# DCDC-LMR16030.net
KiCad netlist of a schematic drawn in Altium Designer
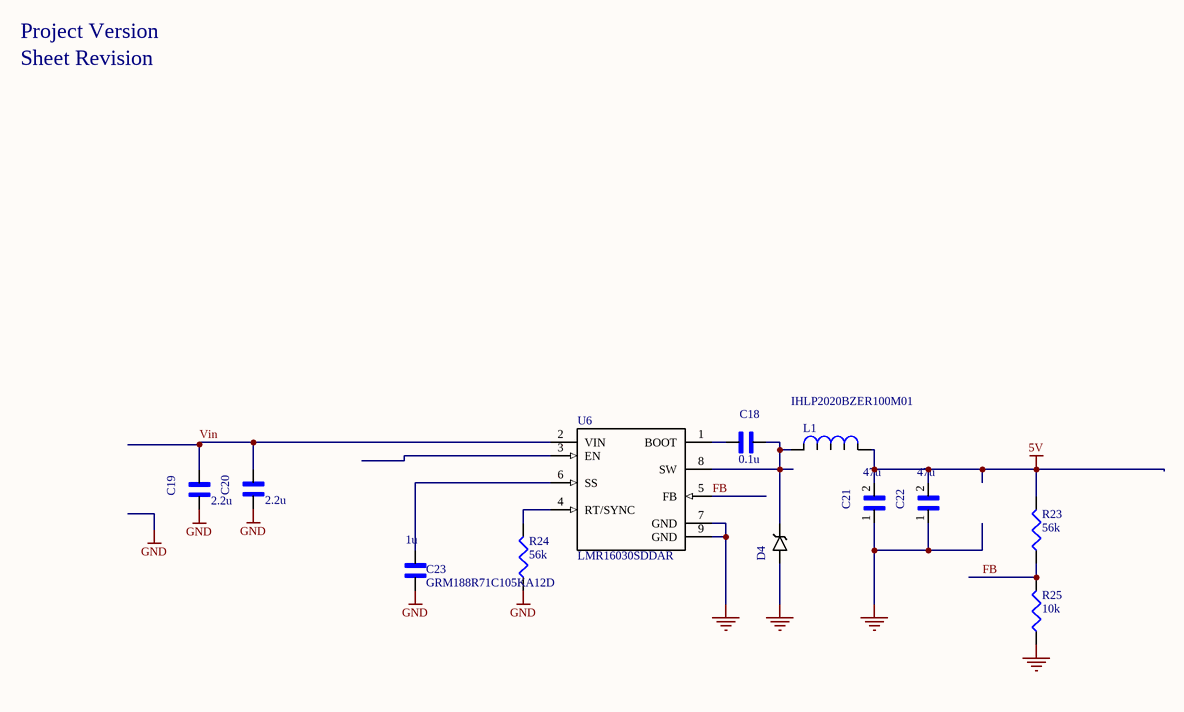
[diagram p0: DCDC-LMR16030.SchDoc]

(export (version "E")
  (design (tool "Eeschema 10.0.6"))
  (components
    (comp (ref "C18")
      (value "0.1u")
      (footprint "*CAPC1608X90")
      (description "Cap Thin Film 0.1uf 50v 0603")
      (fields (field (name "MF") "AVX") (field (name "MP") "GX035C104MAT2-500 or CL10B104JB8NNNC"))
      (libsource (lib "lib") (part "GX035C104MAT2-500"))
    )
    (comp (ref "C19")
      (value "2.2u")
      (footprint "*CAP3216X125N")
      (description "1206 2.2 uF 50 V В±10% Tolerance X7R SMT Multilayer Ceramic Capacitor")
      (fields (field (name "MF") "Murata Electronics") (field (name "MP") "GRM31CR71H225KA88L"))
      (libsource (lib "lib") (part "GRM31CR71H225KA88L"))
    )
    (comp (ref "C20")
      (value "2.2u")
      (footprint "*CAP3216X125N")
      (description "1206 2.2 uF 50 V В±10% Tolerance X7R SMT Multilayer Ceramic Capacitor")
      (fields (field (name "MF") "Murata Electronics") (field (name "MP") "GRM31CR71H225KA88L"))
      (libsource (lib "lib") (part "GRM31CR71H225KA88L"))
    )
    (comp (ref "C21")
      (value "47u")
      (footprint "*CAPC3216X125N")
      (description "Multilayer Ceramic Capacitor, GRM Series, 47 - F, - 10%, X5R, 10 V, 1206 [3216 Metric]")
      (fields (field (name "MF") "Murata Electronics") (field (name "MP") "GRM31CR61A476KE15L"))
      (libsource (lib "lib") (part "GRM31CR61A476KE15L"))
    )
    (comp (ref "C22")
      (value "47u")
      (footprint "*CAPC3216X125N")
      (description "Multilayer Ceramic Capacitor, GRM Series, 47 - F, - 10%, X5R, 10 V, 1206 [3216 Metric]")
      (fields (field (name "MF") "Murata Electronics") (field (name "MP") "GRM31CR61A476KE15L"))
      (libsource (lib "lib") (part "GRM31CR61A476KE15L"))
    )
    (comp (ref "C23")
      (value "GRM188R71C105KA12D")
      (footprint "CAPC1608X90N")
      (description "SMD Capacitor X7R(EIA) with Capacitance: 1.0uF Tol. 10%. Rated Voltage: 16Vdc")
      (fields (field (name "MF") "Murata Electronics") (field (name "ALTIUM_VALUE") "1u"))
      (libsource (lib "lib") (part "GRM188R71C105KA12D"))
    )
    (comp (ref "D4")
      (value "SK56")
      (footprint "*SMB_P6SMB62AT3G(Primary)")
      (description "Диод Шоттки 5А 60В [SMB / DO-214AA]")
      (fields (field (name "MF") "Littelfuse Inc."))
      (libsource (lib "lib") (part "SK56"))
    )
    (comp (ref "L1")
      (value "IHLP2020BZER100M01")
      (footprint "IHLP")
      (description "10ÂµH Shielded Molded Inductor 2.3A 199mOhm Max Nonstandard")
      (fields (field (name "MF") "Vishay Dale"))
      (libsource (lib "lib") (part "IHLP2020BZER100M01"))
    )
    (comp (ref "R23")
      (value "56k")
      (footprint "J1-0603")
      (description "Resistor")
      (fields (field (name "MP") "RC0603FR-0756KL") (field (name "Comment") "Res3"))
      (libsource (lib "Miscellaneous Devices") (part "Res3"))
    )
    (comp (ref "R24")
      (value "56k")
      (footprint "J1-0603")
      (description "Resistor")
      (fields (field (name "MP") "RC0603FR-0756KL") (field (name "Comment") "Res3"))
      (libsource (lib "Miscellaneous Devices") (part "Res3"))
    )
    (comp (ref "R25")
      (value "10k")
      (footprint "J1-0603")
      (description "10 kOhms 1 0.1 W 1 10 W Chip Resistor 0603 1608 Metric Thick Film")
      (fields (field (name "MF") "Yageo or NXP") (field (name "MP") "10K 1% 0603"))
      (libsource (lib "CAN_NODE_MINI") (part "RC0603FR-0710KL"))
    )
    (comp (ref "U6")
      (value "LMR16030SDDAR")
      (footprint "*SOIC127P600X170-9N - duplicate")
      (fields (field (name "MF") "Texas Instruments"))
      (libsource (lib "lib") (part "LMR16030SDDAR"))
    )
  )
  (nets
    (net (code "1") (name "/FB") (class "Default")
      (node (ref "R23") (pin "1") (pinfunction "1_1") (pintype "passive"))
      (node (ref "R25") (pin "2") (pinfunction "2_2") (pintype "passive"))
      (node (ref "U6") (pin "5") (pinfunction "FB_5") (pintype "input"))
    )
    (net (code "2") (name "/Vin") (class "Default")
      (node (ref "C19") (pin "1") (pinfunction "1_1") (pintype "passive"))
      (node (ref "C20") (pin "1") (pinfunction "1_1") (pintype "passive"))
      (node (ref "U6") (pin "2") (pinfunction "VIN_2") (pintype "power_in"))
    )
    (net (code "3") (name "5V") (class "Default")
      (node (ref "C21") (pin "2") (pinfunction "2_2") (pintype "passive"))
      (node (ref "C22") (pin "2") (pinfunction "2_2") (pintype "passive"))
      (node (ref "L1") (pin "1") (pinfunction "1_1") (pintype "passive"))
      (node (ref "R23") (pin "2") (pinfunction "2_2") (pintype "passive"))
    )
    (net (code "4") (name "GND") (class "Default")
      (node (ref "C19") (pin "2") (pinfunction "2_2") (pintype "passive"))
      (node (ref "C20") (pin "2") (pinfunction "2_2") (pintype "passive"))
      (node (ref "C21") (pin "1") (pinfunction "1_1") (pintype "passive"))
      (node (ref "C22") (pin "1") (pinfunction "1_1") (pintype "passive"))
      (node (ref "C23") (pin "1") (pinfunction "1_1") (pintype "passive"))
      (node (ref "D4") (pin "A") (pinfunction "A_A") (pintype "power_in"))
      (node (ref "R24") (pin "1") (pinfunction "1_1") (pintype "passive"))
      (node (ref "R25") (pin "1") (pinfunction "1_1") (pintype "passive"))
      (node (ref "U6") (pin "7") (pinfunction "GND_7") (pintype "power_in"))
      (node (ref "U6") (pin "9") (pinfunction "GND_9") (pintype "power_in"))
    )
    (net (code "5") (name "Net-(U6-BOOT)") (class "Default")
      (node (ref "C18") (pin "2") (pinfunction "2_2") (pintype "passive"))
      (node (ref "U6") (pin "1") (pinfunction "BOOT_1") (pintype "power_in"))
    )
    (net (code "6") (name "Net-(U6-RT{slash}SYNC)") (class "Default")
      (node (ref "R24") (pin "2") (pinfunction "2_2") (pintype "passive"))
      (node (ref "U6") (pin "4") (pinfunction "RT/SYNC_4") (pintype "input"))
    )
    (net (code "7") (name "Net-(U6-SS)") (class "Default")
      (node (ref "C23") (pin "2") (pinfunction "2_2") (pintype "passive"))
      (node (ref "U6") (pin "6") (pinfunction "SS_6") (pintype "input"))
    )
    (net (code "8") (name "Net-(U6-SW)") (class "Default")
      (node (ref "C18") (pin "1") (pinfunction "1_1") (pintype "passive"))
      (node (ref "D4") (pin "C") (pinfunction "C_C") (pintype "power_in"))
      (node (ref "L1") (pin "2") (pinfunction "2_2") (pintype "passive"))
      (node (ref "U6") (pin "8") (pinfunction "SW_8") (pintype "power_in"))
    )
    (net (code "9") (name "unconnected-(U6-EN-Pad3)") (class "Default")
      (node (ref "U6") (pin "3") (pinfunction "EN_3") (pintype "input"))
    )
  )
)
